# 7_Accumulator_Indicator.net
KiCad netlist of a schematic drawn in Altium Designer
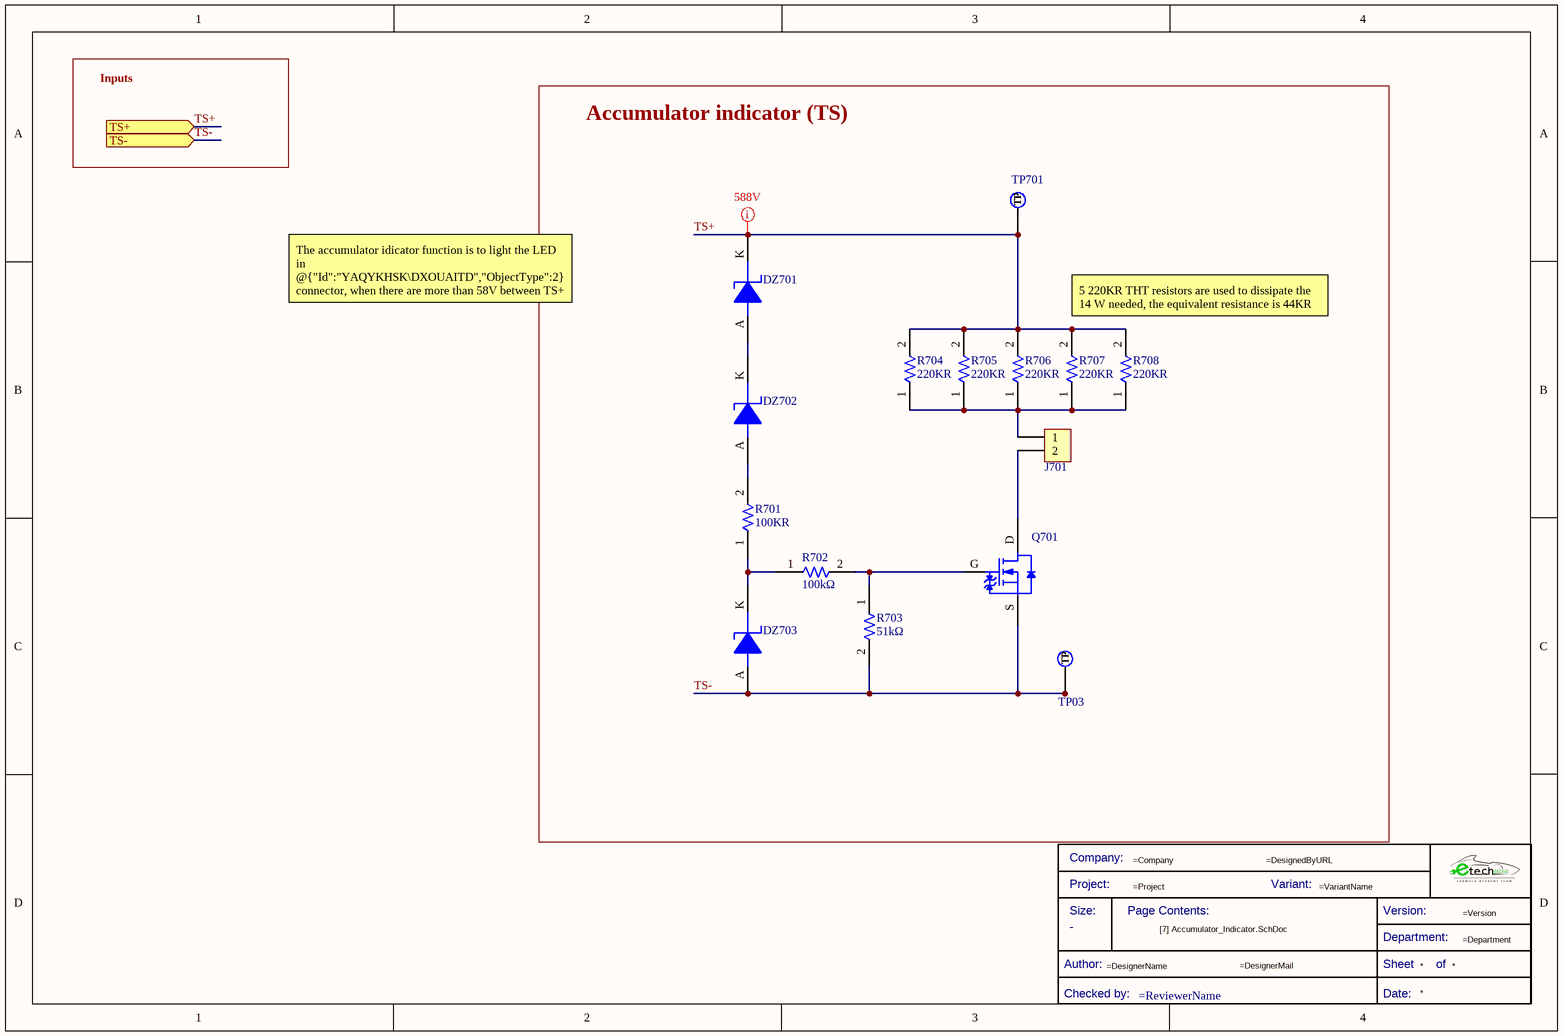
[diagram p0: [7] Accumulator_Indicator.SchDoc]

(export (version "E")
  (design (tool "Eeschema 10.0.6"))
  (components
    (comp (ref "*")
      (value "Title Block_template")
      (description "Standard Title Block")
      (fields
        (field (name "SIZE") "-")
        (field (name ".CREATOR") "GP")
        (field (name ".PCBCHECK") "GP")
        (field (name ".SCHCHECK") "GP")
      )
      (libsource (lib "e-Tech_Racing") (part "Title Block_template"))
    )
    (comp (ref "DZ701")
      (value "DZ_24V")
      (footprint "DZ_24V")
      (description "3.0 W Zener Diode Voltage Regulator 24 V (Automotive)")
      (fields
        (field (name "MANUFACTURER") "Diodes")
        (field (name "MANUFACTURER PART NUMBER") "BZT52C5V1-7-F")
      )
      (libsource (lib "Semiconductor") (part "DZ_24V"))
    )
    (comp (ref "DZ702")
      (value "DZ_24V")
      (footprint "DZ_24V")
      (description "3.0 W Zener Diode Voltage Regulator 24 V (Automotive)")
      (fields
        (field (name "MANUFACTURER") "Diodes")
        (field (name "MANUFACTURER PART NUMBER") "BZT52C5V1-7-F")
      )
      (libsource (lib "Semiconductor") (part "DZ_24V"))
    )
    (comp (ref "DZ703")
      (value "DZ_10V")
      (footprint "SOD123")
      (description "BZT52C5V1 Series 500 mW 10V 10 mA Surface Mount Zener Diode - SOD-123")
      (fields
        (field (name "MANUFACTURER") "Diodes")
        (field (name "MANUFACTURER PART NUMBER") "BZT52C5V1-7-F")
      )
      (libsource (lib "Semiconductor") (part "DZ_10V"))
    )
    (comp (ref "J701")
      (value "105309-2202")
      (footprint "J_NanoFit_1x2_V")
      (fields (field (name "MANUFACTURER") "Molex"))
      (libsource (lib "Electromechanical") (part "J_Nanofit_1x2_V"))
    )
    (comp (ref "Q701")
      (value "IRLR2905")
      (footprint "IRLR2905")
      (description "MOSFET N-CH 55V 42A DPAK")
      (fields
        (field (name "MANUFACTURER") "Infineon")
        (field (name "MANUFACTURER PART NUMBER") "IRLR2905TRPBF")
      )
      (libsource (lib "Semiconductor") (part "TRT-NCH-55V-42A"))
    )
    (comp (ref "R701")
      (value "100KR")
      (footprint "THT_3W_Resistor")
      (libsource (lib "Passives") (part "R100K_3W_THT"))
    )
    (comp (ref "R702")
      (value "CRG1206F100R")
      (footprint "R1206FTK-W")
      (description "Res Thick Film 1206 100 Ohm 1% 0.25W(1/4W) ±200ppm/C Pad SMD T/R")
      (fields
        (field (name "MANUFACTURER") "TE Connectivity")
        (field (name "TOLERANCE") "1%")
        (field (name "RESISTANCE") "100kΩ")
        (field (name ".CREATOR") "AC")
      )
      (libsource (lib "Passives") (part "R100-1206FTK"))
    )
    (comp (ref "R703")
      (value "CRCW120610K0FKEA")
      (footprint "R1206FTK-W")
      (description "Res Thick Film 1206 51K Ohm 1% 1/4W ±100ppm/°C Molded SMD SMD Punched Carrier T/R")
      (fields
        (field (name "MANUFACTURER") "Panasonic")
        (field (name "MANUFACTURER PART NUMBER") "ERJ-S08F5102V")
        (field (name "RESISTANCE") "51kΩ")
        (field (name ".CREATOR") "DO")
      )
      (libsource (lib "Passives") (part "R51k-1206FTK"))
    )
    (comp (ref "R704")
      (value "220KR")
      (footprint "THT_3W_Resistor")
      (libsource (lib "Passives") (part "R220K_3W_THT"))
    )
    (comp (ref "R705")
      (value "220KR")
      (footprint "THT_3W_Resistor")
      (libsource (lib "Passives") (part "R220K_3W_THT"))
    )
    (comp (ref "R706")
      (value "220KR")
      (footprint "THT_3W_Resistor")
      (libsource (lib "Passives") (part "R220K_3W_THT"))
    )
    (comp (ref "R707")
      (value "220KR")
      (footprint "THT_3W_Resistor")
      (libsource (lib "Passives") (part "R220K_3W_THT"))
    )
    (comp (ref "R708")
      (value "220KR")
      (footprint "THT_3W_Resistor")
      (libsource (lib "Passives") (part "R220K_3W_THT"))
    )
    (comp (ref "TP03")
      (value "TestPoint")
      (footprint "TestPoint")
      (description "Test Point 1x1 mm")
      (fields (field (name ".CREATOR") "GP") (field (name ".PCBCHECK") "GP") (field (name ".SCHCHECK") "GP"))
      (libsource (lib "e-Tech_Racing") (part "TestPoint"))
    )
    (comp (ref "TP701")
      (value "TestPoint")
      (footprint "TestPoint")
      (description "Test Point 1x1 mm")
      (fields (field (name ".CREATOR") "GP") (field (name ".PCBCHECK") "GP") (field (name ".SCHCHECK") "GP"))
      (libsource (lib "e-Tech_Racing") (part "TestPoint"))
    )
  )
  (nets
    (net (code "1") (name "/TS+") (class "Default")
      (node (ref "DZ701") (pin "K") (pinfunction "K_K") (pintype "passive"))
      (node (ref "R704") (pin "2") (pinfunction "2_2") (pintype "passive"))
      (node (ref "R705") (pin "2") (pinfunction "2_2") (pintype "passive"))
      (node (ref "R706") (pin "2") (pinfunction "2_2") (pintype "passive"))
      (node (ref "R707") (pin "2") (pinfunction "2_2") (pintype "passive"))
      (node (ref "R708") (pin "2") (pinfunction "2_2") (pintype "passive"))
      (node (ref "TP701") (pin "1") (pinfunction "TP_1") (pintype "passive"))
    )
    (net (code "2") (name "/TS-") (class "Default")
      (node (ref "DZ703") (pin "A") (pinfunction "A_A") (pintype "passive"))
      (node (ref "Q701") (pin "S") (pinfunction "S_S") (pintype "passive"))
      (node (ref "R703") (pin "2") (pinfunction "2_2") (pintype "passive"))
      (node (ref "TP03") (pin "1") (pinfunction "TP_1") (pintype "passive"))
    )
    (net (code "3") (name "Net-(DZ701-PadA)") (class "Default")
      (node (ref "DZ701") (pin "A") (pinfunction "A_A") (pintype "passive"))
      (node (ref "DZ702") (pin "K") (pinfunction "K_K") (pintype "passive"))
    )
    (net (code "4") (name "Net-(DZ702-PadA)") (class "Default")
      (node (ref "DZ702") (pin "A") (pinfunction "A_A") (pintype "passive"))
      (node (ref "R701") (pin "2") (pinfunction "2_2") (pintype "passive"))
    )
    (net (code "5") (name "Net-(DZ703-PadK)") (class "Default")
      (node (ref "DZ703") (pin "K") (pinfunction "K_K") (pintype "passive"))
      (node (ref "R701") (pin "1") (pinfunction "1_1") (pintype "passive"))
      (node (ref "R702") (pin "1") (pinfunction "1_1") (pintype "passive"))
    )
    (net (code "6") (name "Net-(J701-Pad1)") (class "Default")
      (node (ref "J701") (pin "1") (pinfunction "1_1") (pintype "passive"))
      (node (ref "R704") (pin "1") (pinfunction "1_1") (pintype "passive"))
      (node (ref "R705") (pin "1") (pinfunction "1_1") (pintype "passive"))
      (node (ref "R706") (pin "1") (pinfunction "1_1") (pintype "passive"))
      (node (ref "R707") (pin "1") (pinfunction "1_1") (pintype "passive"))
      (node (ref "R708") (pin "1") (pinfunction "1_1") (pintype "passive"))
    )
    (net (code "7") (name "Net-(J701-Pad2)") (class "Default")
      (node (ref "J701") (pin "2") (pinfunction "2_2") (pintype "passive"))
      (node (ref "Q701") (pin "D") (pinfunction "D_D") (pintype "passive"))
    )
    (net (code "8") (name "Net-(Q701-PadG)") (class "Default")
      (node (ref "Q701") (pin "G") (pinfunction "G_G") (pintype "passive"))
      (node (ref "R702") (pin "2") (pinfunction "2_2") (pintype "passive"))
      (node (ref "R703") (pin "1") (pinfunction "1_1") (pintype "passive"))
    )
  )
)
